# Charging_Indicator_V1_0.net
KiCad netlist of a schematic drawn in EasyEDA
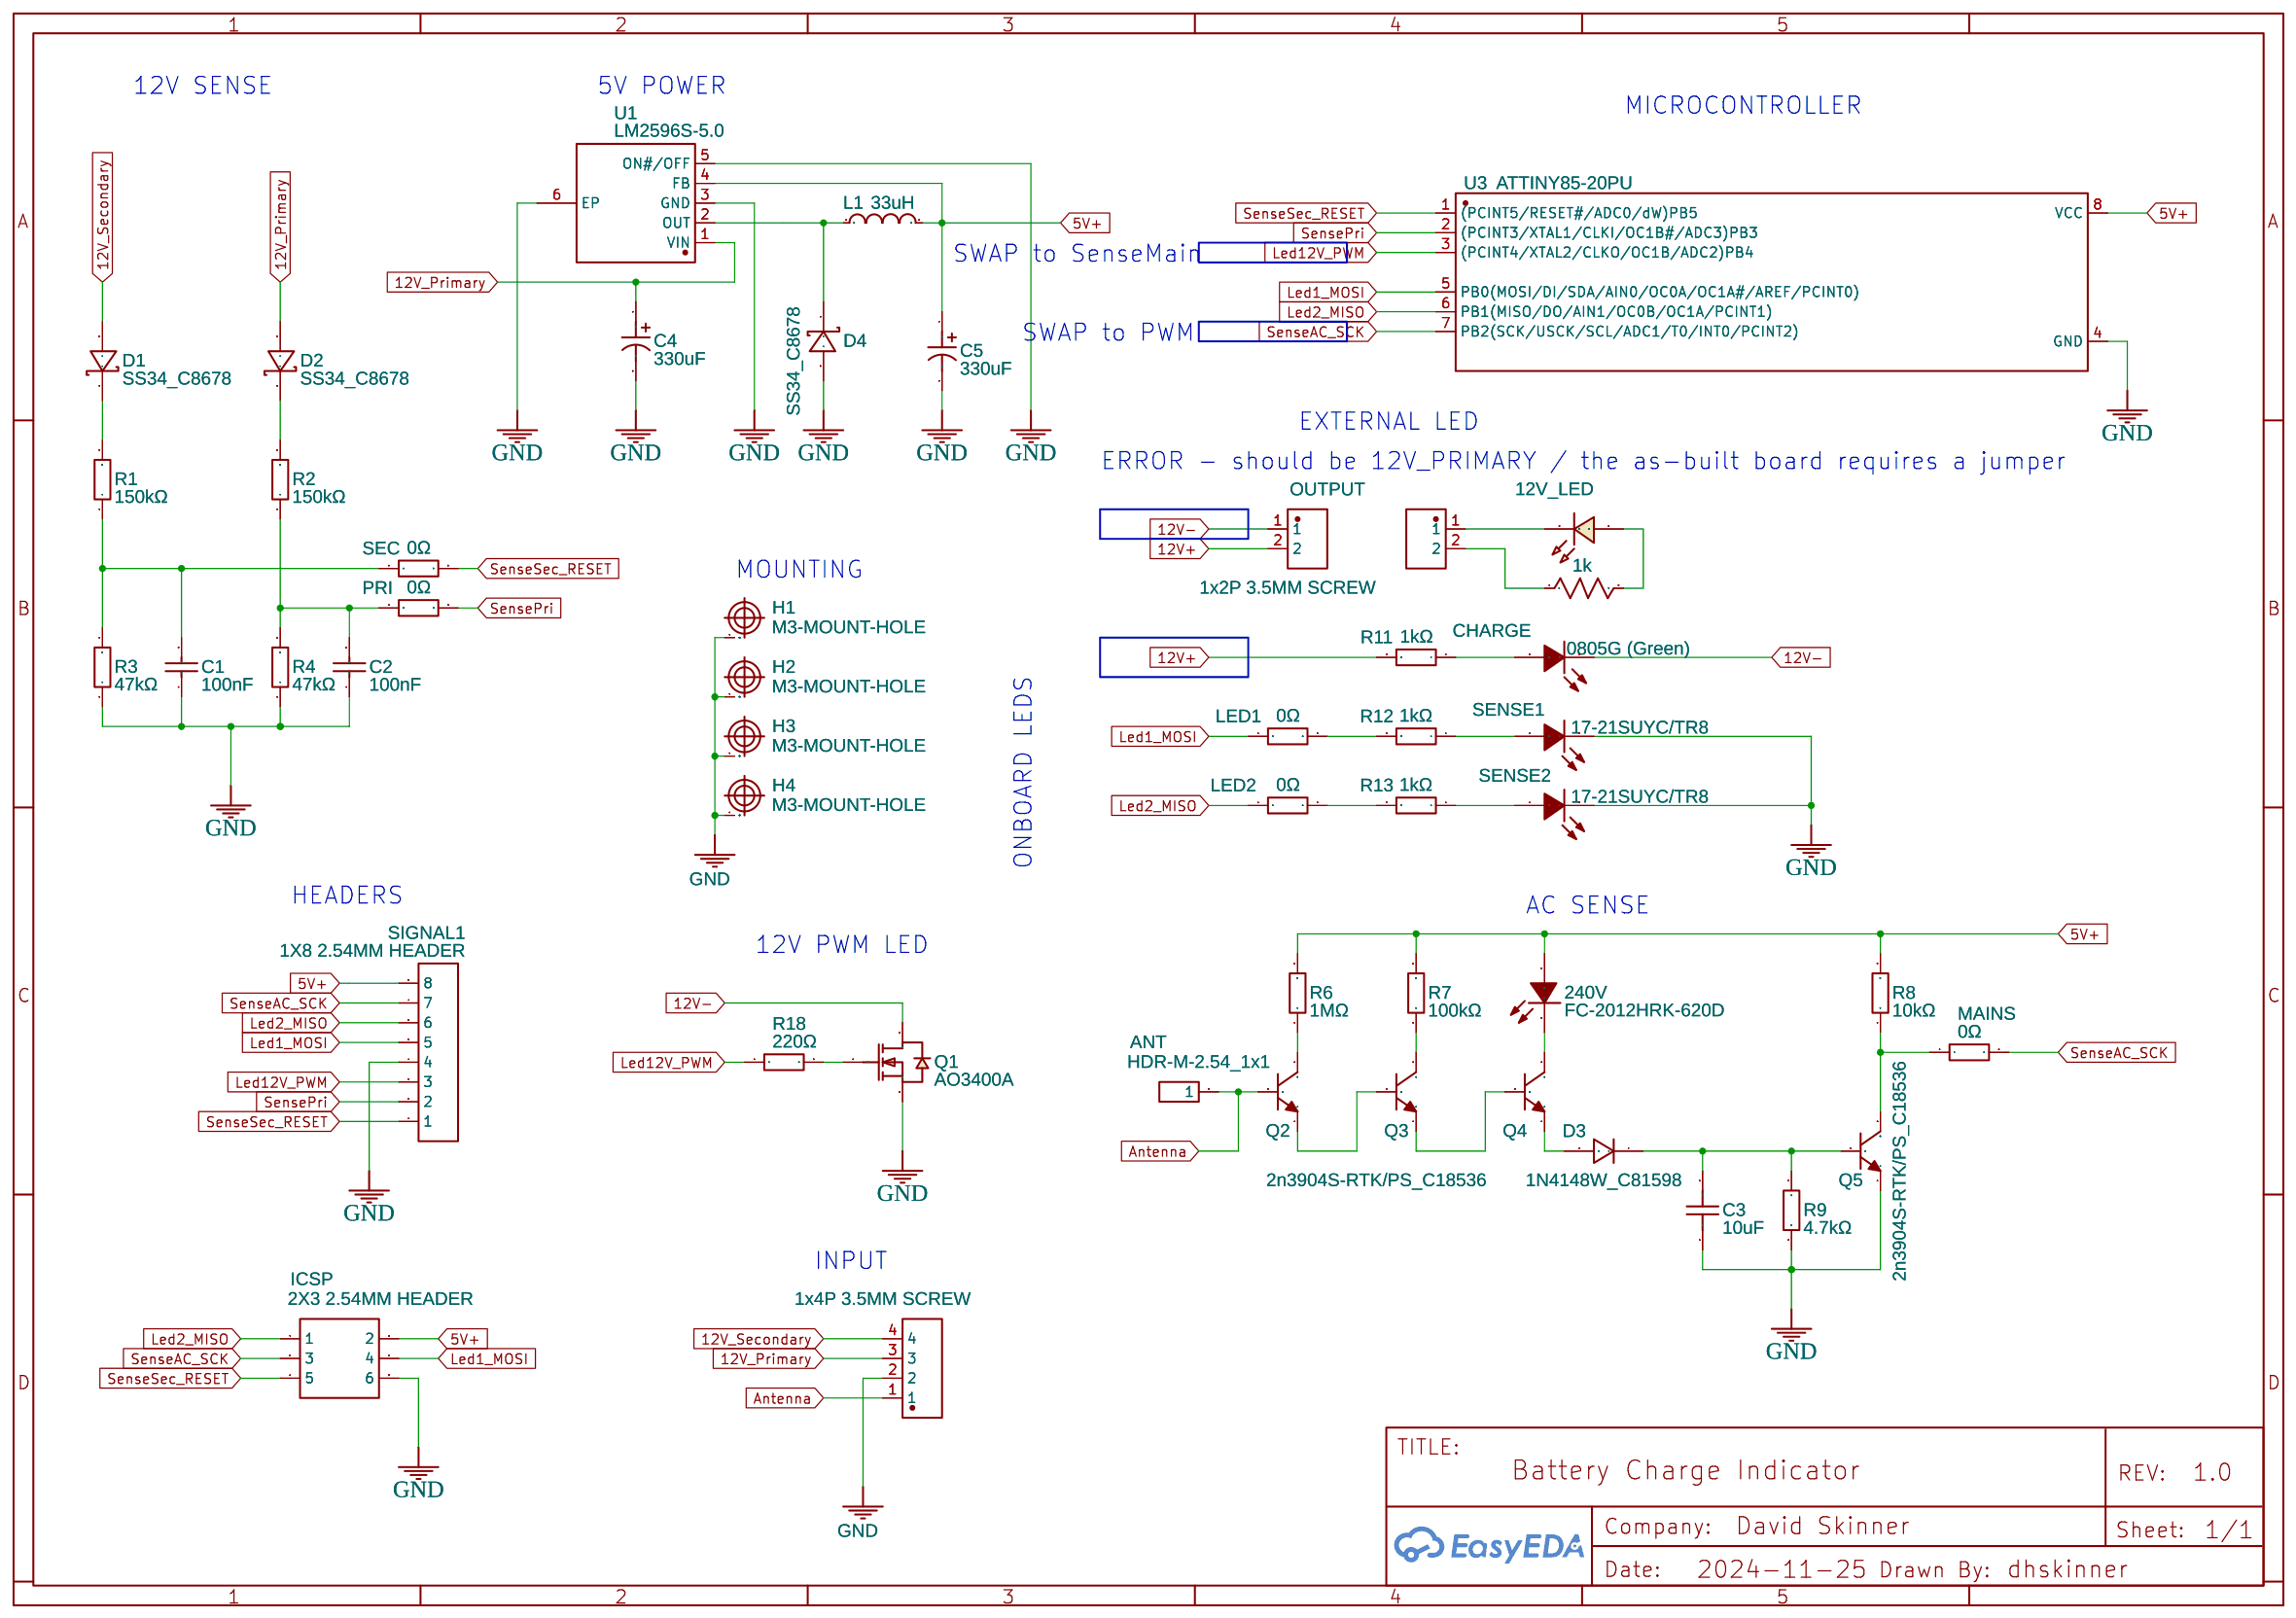
[diagram p0: Sheet_1]
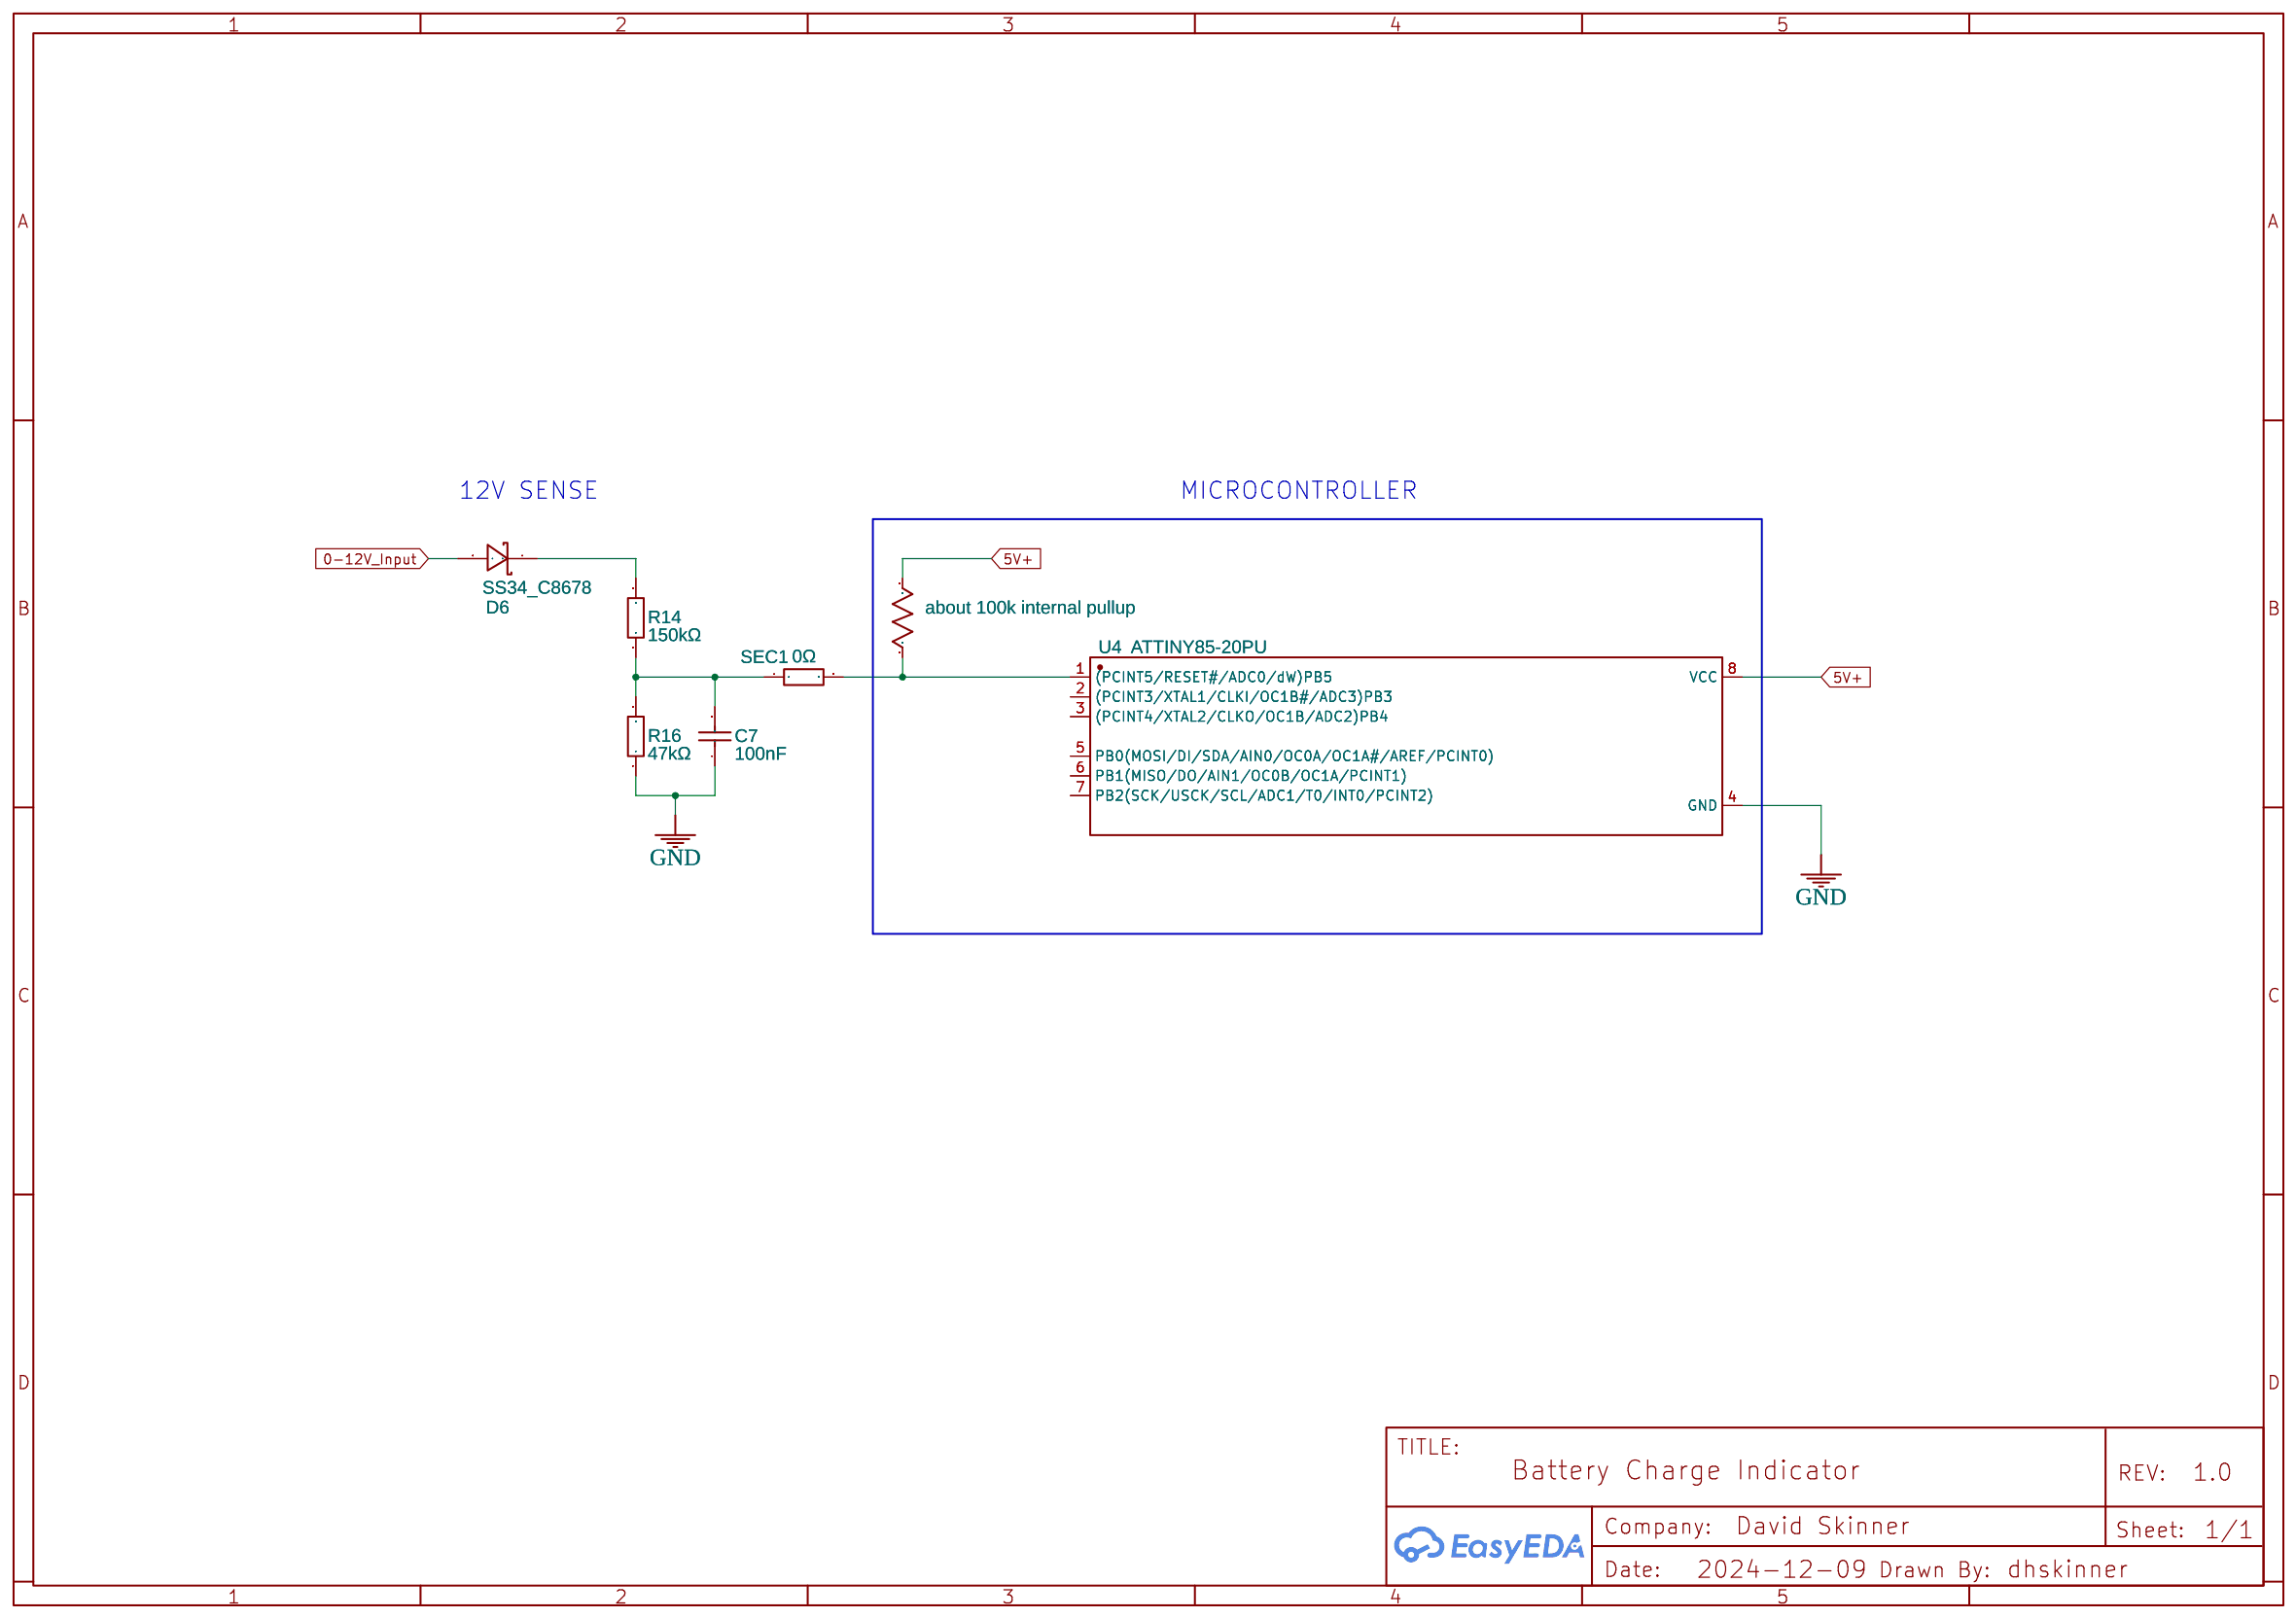
[diagram p1: Sheet_2]
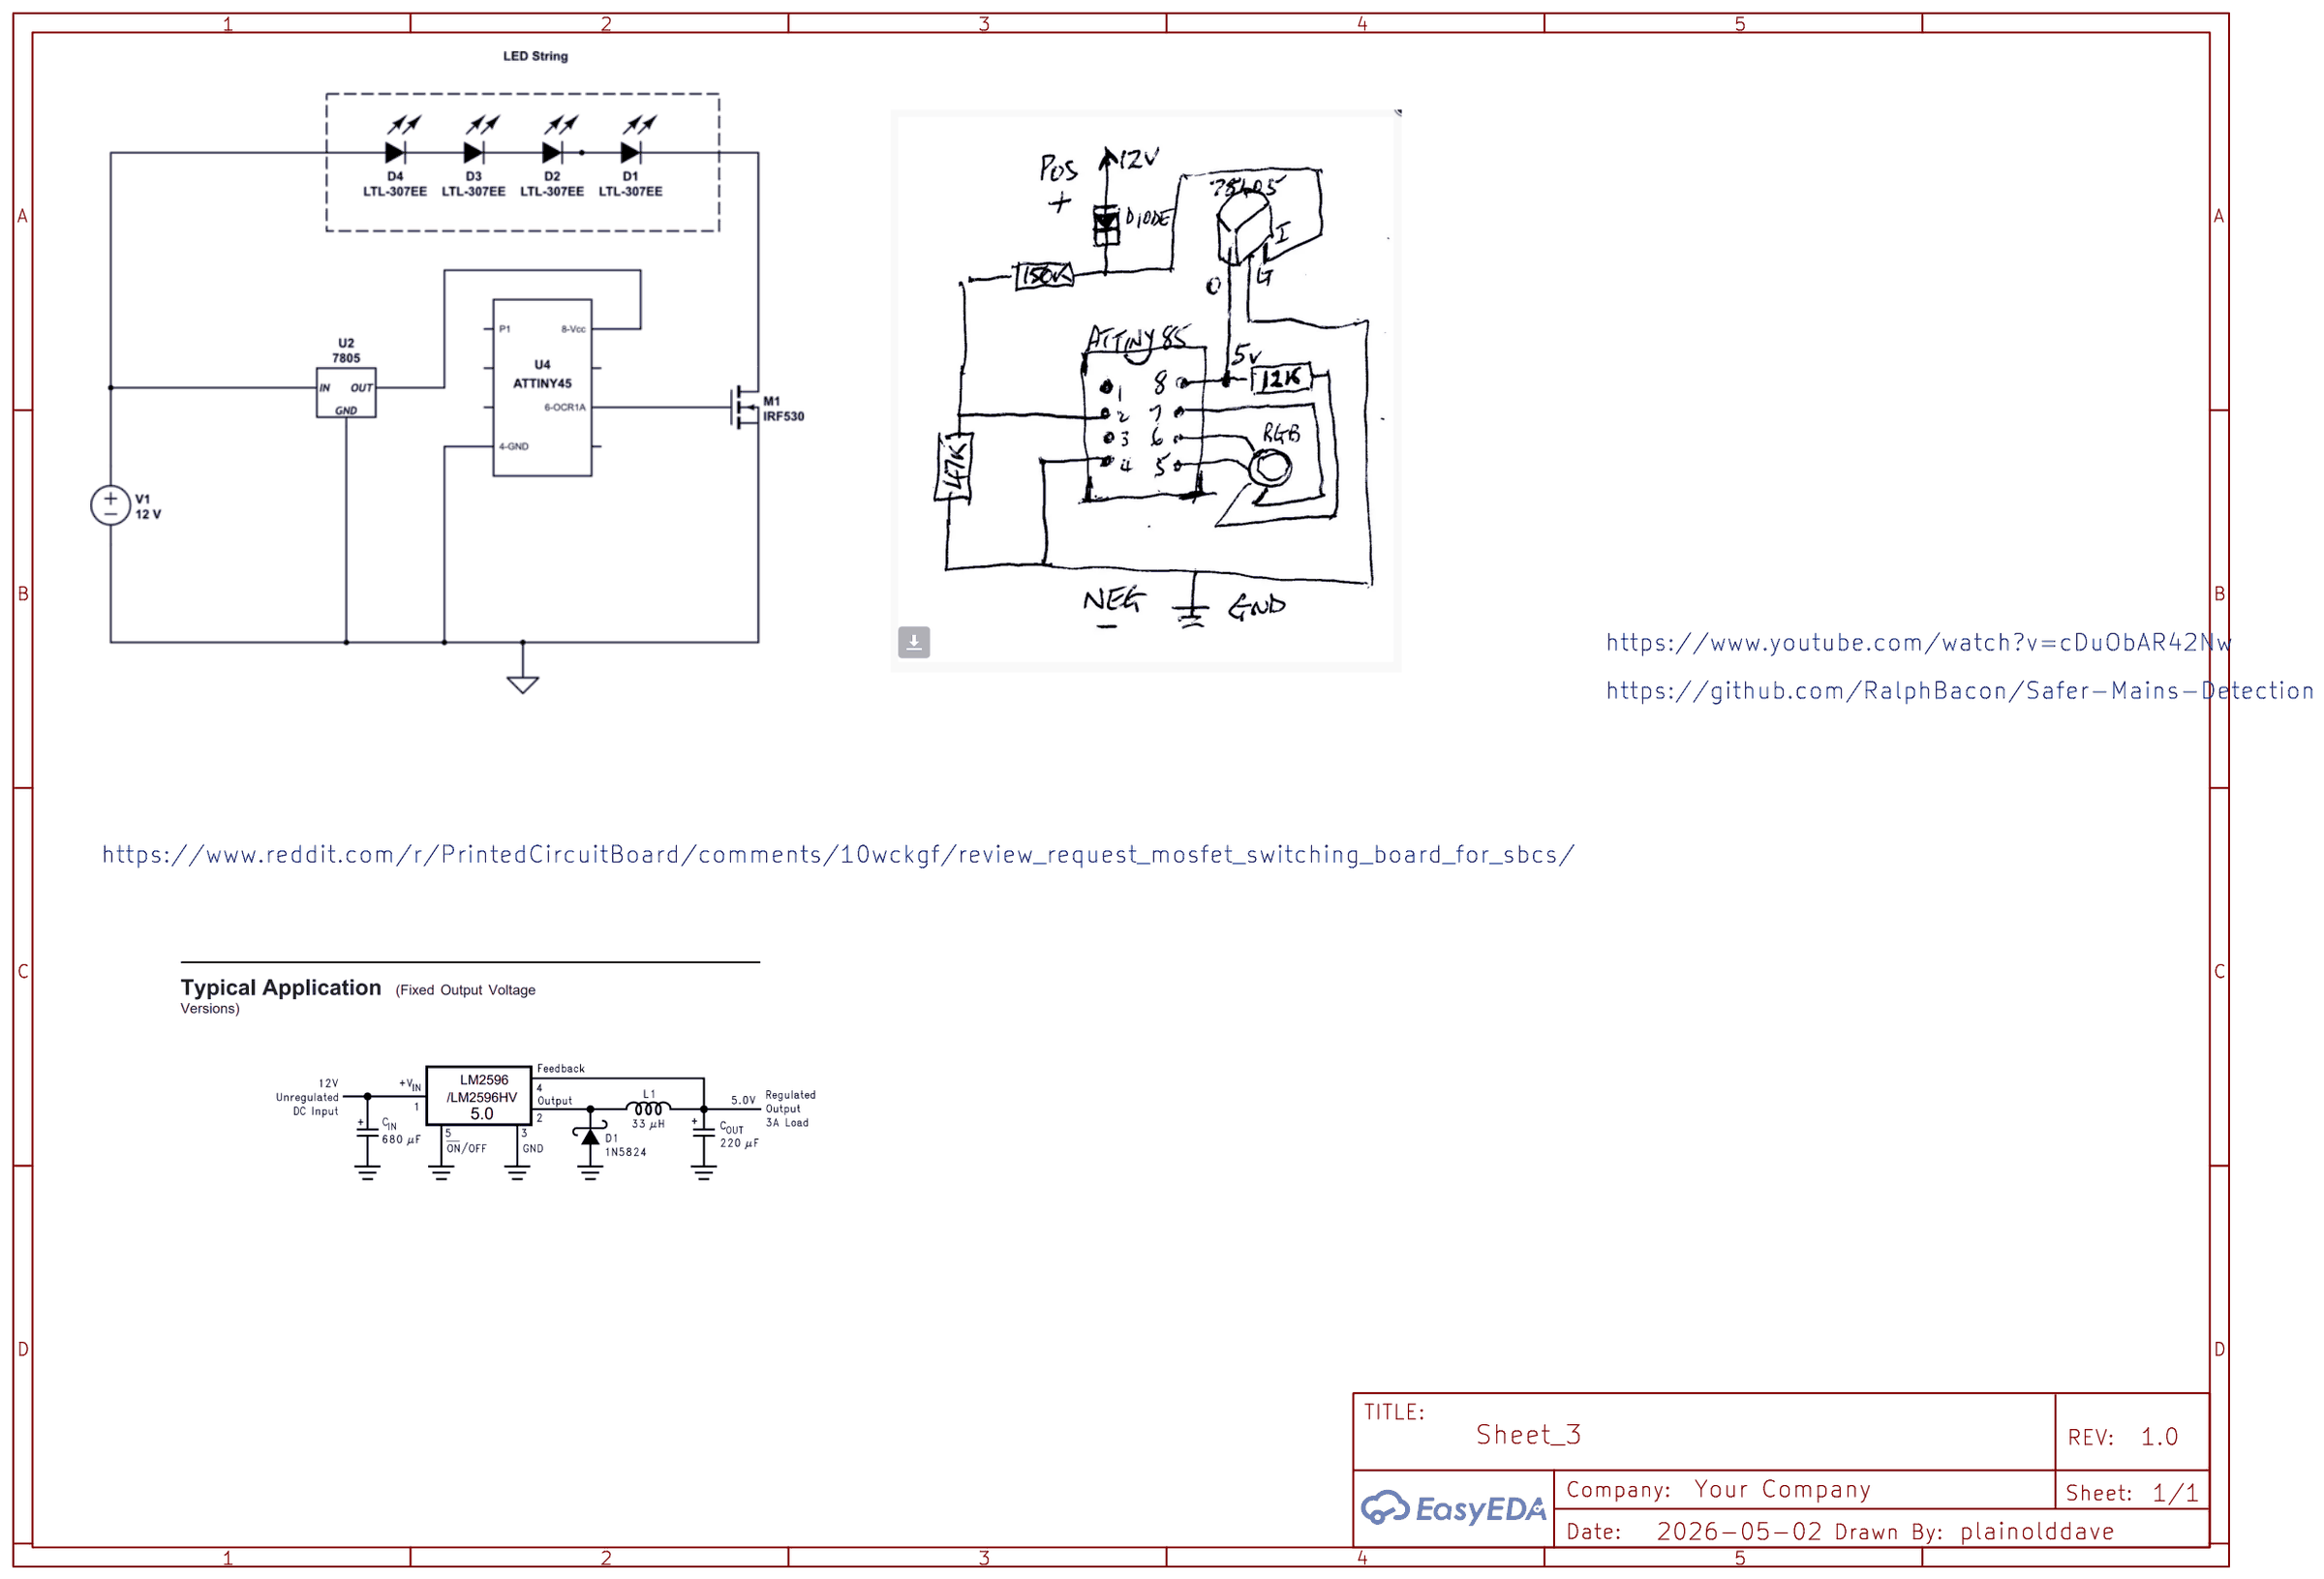
[diagram p2: Notes]

(export (version "E")
  (design (tool "Eeschema 10.0.6"))
  (components
    (comp (ref "12V_LED")
      (value "LED-TH-5mm_G")
      (fields
        (field (name "Manufacturer Part") "333-2SYGD/S530-E2")
        (field (name "Manufacturer") "EVERLIGHT(台湾亿光)")
      )
      (libsource (lib "") (part "LED-TH-5mm_G"))
    )
    (comp (ref "240V")
      (value "FC-2012HRK-620D")
      (fields (field (name "Manufacturer Part") "NCD0805R1") (field (name "Manufacturer") "国星光电"))
      (libsource (lib "") (part "FC-2012HRK-620D"))
    )
    (comp (ref "ANT") (value "HDR-M-2.54_1x1") (libsource (lib "") (part "HDR-M-2.54_1x1")))
    (comp (ref "C1")
      (value "100nF")
      (fields
        (field (name "Manufacturer Part") "CL21B104KCFNNNE")
        (field (name "Manufacturer") "SAMSUNG(三星)")
      )
      (libsource (lib "") (part "CL21B104KCFNNNE"))
    )
    (comp (ref "C2")
      (value "100nF")
      (fields
        (field (name "Manufacturer Part") "CL21B104KCFNNNE")
        (field (name "Manufacturer") "SAMSUNG(三星)")
      )
      (libsource (lib "") (part "CL21B104KCFNNNE"))
    )
    (comp (ref "C3")
      (value "10uF")
      (fields
        (field (name "Manufacturer Part") "CL10A106MA8NRNC")
        (field (name "Manufacturer") "SAMSUNG(三星)")
      )
      (libsource (lib "") (part "CL10A106MA8NRNC"))
    )
    (comp (ref "C4")
      (value "330uF")
      (fields (field (name "Manufacturer Part") "HV0J337M0605PZ") (field (name "Manufacturer") "HONOR(荣誉)"))
      (libsource (lib "") (part "HV0J337M0605PZ"))
    )
    (comp (ref "C5")
      (value "330uF")
      (fields (field (name "Manufacturer Part") "HV0J337M0605PZ") (field (name "Manufacturer") "HONOR(荣誉)"))
      (libsource (lib "") (part "HV0J337M0605PZ"))
    )
    (comp (ref "CHARGE")
      (value "0805G (Green)")
      (fields (field (name "Manufacturer Part") "KT-0805G") (field (name "Manufacturer") "KENTO"))
      (libsource (lib "") (part "0805G (Green)"))
    )
    (comp (ref "D1")
      (value "SS34_C8678")
      (fields (field (name "Manufacturer Part") "SS34") (field (name "Manufacturer") "MDD(辰达半导体)"))
      (libsource (lib "") (part "SS34_C8678_1"))
    )
    (comp (ref "D2")
      (value "SS34_C8678")
      (fields (field (name "Manufacturer Part") "SS34") (field (name "Manufacturer") "MDD(辰达半导体)"))
      (libsource (lib "") (part "SS34_C8678_1"))
    )
    (comp (ref "D3")
      (value "1N4148W_C81598")
      (fields (field (name "Manufacturer Part") "1N4148W") (field (name "Manufacturer") "ST(先科)"))
      (libsource (lib "") (part "1N4148W_C81598"))
    )
    (comp (ref "D4")
      (value "SS34_C8678")
      (fields (field (name "Manufacturer Part") "SS34") (field (name "Manufacturer") "MDD(辰达半导体)"))
      (libsource (lib "") (part "SS34_C8678"))
    )
    (comp (ref "H1") (value "M3-MOUNT-HOLE") (libsource (lib "") (part "M3-MOUNT-HOLE")))
    (comp (ref "H2") (value "M3-MOUNT-HOLE") (libsource (lib "") (part "M3-MOUNT-HOLE")))
    (comp (ref "H3") (value "M3-MOUNT-HOLE") (libsource (lib "") (part "M3-MOUNT-HOLE")))
    (comp (ref "H4") (value "M3-MOUNT-HOLE") (libsource (lib "") (part "M3-MOUNT-HOLE")))
    (comp (ref "ICSP") (value "2X3 2.54MM HEADER") (libsource (lib "") (part "HDR-M-2.54_2x3")))
    (comp (ref "INPUT")
      (value "1x4P 3.5MM SCREW")
      (fields (field (name "Manufacturer Part") "XY350V-3.5-4P") (field (name "Manufacturer") "--"))
      (libsource (lib "") (part "XY350V-3.5-4P"))
    )
    (comp (ref "L1")
      (value "33uH")
      (fields
        (field (name "Manufacturer Part") "SLH1207S330MTT")
        (field (name "Manufacturer") "Sunltech(韩国顺磁)")
      )
      (libsource (lib "") (part "SLH1207S330MTT"))
    )
    (comp (ref "LED1")
      (value "0Ω")
      (fields
        (field (name "Manufacturer Part") "0603WAF0000T5E")
        (field (name "Manufacturer") "UNI-ROYAL(厚声)")
      )
      (libsource (lib "") (part "0603WAF0000T5E_3"))
    )
    (comp (ref "LED2")
      (value "0Ω")
      (fields
        (field (name "Manufacturer Part") "0603WAF0000T5E")
        (field (name "Manufacturer") "UNI-ROYAL(厚声)")
      )
      (libsource (lib "") (part "0603WAF0000T5E_3"))
    )
    (comp (ref "MAINS")
      (value "0Ω")
      (fields
        (field (name "Manufacturer Part") "0603WAF0000T5E")
        (field (name "Manufacturer") "UNI-ROYAL(厚声)")
      )
      (libsource (lib "") (part "0603WAF0000T5E_2"))
    )
    (comp (ref "OUTPUT")
      (value "1x2P 3.5MM SCREW")
      (fields (field (name "Manufacturer Part") "JL124D-35002G01") (field (name "Manufacturer") "JILN(锦凌)"))
      (libsource (lib "") (part "JL124D-35002G01"))
    )
    (comp (ref "PRI")
      (value "0Ω")
      (fields
        (field (name "Manufacturer Part") "0603WAF0000T5E")
        (field (name "Manufacturer") "UNI-ROYAL(厚声)")
      )
      (libsource (lib "") (part "0603WAF0000T5E_1"))
    )
    (comp (ref "Q1")
      (value "AO3400A")
      (fields (field (name "Manufacturer") "AOS"))
      (libsource (lib "") (part "AO3400A"))
    )
    (comp (ref "Q2")
      (value "2n3904S-RTK/PS_C18536")
      (fields (field (name "Manufacturer Part") "2N3904S-RTK/PS") (field (name "Manufacturer") "KEC"))
      (libsource (lib "") (part "2n3904S-RTK/PS_C18536"))
    )
    (comp (ref "Q3")
      (value "2n3904S-RTK/PS_C18536")
      (fields (field (name "Manufacturer Part") "2N3904S-RTK/PS") (field (name "Manufacturer") "KEC"))
      (libsource (lib "") (part "2n3904S-RTK/PS_C18536"))
    )
    (comp (ref "Q4")
      (value "2n3904S-RTK/PS_C18536")
      (fields (field (name "Manufacturer Part") "2N3904S-RTK/PS") (field (name "Manufacturer") "KEC"))
      (libsource (lib "") (part "2n3904S-RTK/PS_C18536"))
    )
    (comp (ref "Q5")
      (value "2n3904S-RTK/PS_C18536")
      (fields (field (name "Manufacturer Part") "2N3904S-RTK/PS") (field (name "Manufacturer") "KEC"))
      (libsource (lib "") (part "2n3904S-RTK/PS_C18536"))
    )
    (comp (ref "R1")
      (value "150kΩ")
      (fields
        (field (name "Manufacturer Part") "0805W8F1503T5E")
        (field (name "Manufacturer") "UNI-ROYAL(厚声)")
      )
      (libsource (lib "") (part "0805W8F1503T5E"))
    )
    (comp (ref "R2")
      (value "150kΩ")
      (fields
        (field (name "Manufacturer Part") "0805W8F1503T5E")
        (field (name "Manufacturer") "UNI-ROYAL(厚声)")
      )
      (libsource (lib "") (part "0805W8F1503T5E"))
    )
    (comp (ref "R3")
      (value "47kΩ")
      (fields
        (field (name "Manufacturer Part") "0805W8F4702T5E")
        (field (name "Manufacturer") "UNI-ROYAL(厚声)")
      )
      (libsource (lib "") (part "0805W8F4702T5E"))
    )
    (comp (ref "R4")
      (value "47kΩ")
      (fields
        (field (name "Manufacturer Part") "0805W8F4702T5E")
        (field (name "Manufacturer") "UNI-ROYAL(厚声)")
      )
      (libsource (lib "") (part "0805W8F4702T5E"))
    )
    (comp (ref "R5") (value "1k") (libsource (lib "") (part "R_AXIAL-0.4_US")))
    (comp (ref "R6")
      (value "1MΩ")
      (fields
        (field (name "Manufacturer Part") "0603WAF1004T5E")
        (field (name "Manufacturer") "UNI-ROYAL(厚声)")
      )
      (libsource (lib "") (part "0603WAF1004T5E"))
    )
    (comp (ref "R7")
      (value "100kΩ")
      (fields
        (field (name "Manufacturer Part") "1206W4F1003T5E")
        (field (name "Manufacturer") "UNI-ROYAL(厚声)")
      )
      (libsource (lib "") (part "1206W4F1003T5E"))
    )
    (comp (ref "R8")
      (value "10kΩ")
      (fields
        (field (name "Manufacturer Part") "0603WAF1002T5E")
        (field (name "Manufacturer") "UNI-ROYAL(厚声)")
      )
      (libsource (lib "") (part "0603WAF1002T5E"))
    )
    (comp (ref "R9")
      (value "4.7kΩ")
      (fields
        (field (name "Manufacturer Part") "1206W4F4701T5E")
        (field (name "Manufacturer") "UNI-ROYAL(厚声)")
      )
      (libsource (lib "") (part "1206W4F4701T5E"))
    )
    (comp (ref "R11")
      (value "1kΩ")
      (fields
        (field (name "Manufacturer Part") "0805W8F1001T5E")
        (field (name "Manufacturer") "UNI-ROYAL(厚声)")
      )
      (libsource (lib "") (part "0805W8F1001T5E"))
    )
    (comp (ref "R12")
      (value "1kΩ")
      (fields
        (field (name "Manufacturer Part") "0805W8F1001T5E")
        (field (name "Manufacturer") "UNI-ROYAL(厚声)")
      )
      (libsource (lib "") (part "0805W8F1001T5E"))
    )
    (comp (ref "R13")
      (value "1kΩ")
      (fields
        (field (name "Manufacturer Part") "0805W8F1001T5E")
        (field (name "Manufacturer") "UNI-ROYAL(厚声)")
      )
      (libsource (lib "") (part "0805W8F1001T5E"))
    )
    (comp (ref "R18")
      (value "220Ω")
      (fields
        (field (name "Manufacturer Part") "0603WAF2200T5E")
        (field (name "Manufacturer") "UNI-ROYAL(厚声)")
      )
      (libsource (lib "") (part "0603WAF2200T5E"))
    )
    (comp (ref "SEC")
      (value "0Ω")
      (fields
        (field (name "Manufacturer Part") "0603WAF0000T5E")
        (field (name "Manufacturer") "UNI-ROYAL(厚声)")
      )
      (libsource (lib "") (part "0603WAF0000T5E"))
    )
    (comp (ref "SENSE1")
      (value "17-21SUYC/TR8")
      (fields (field (name "Manufacturer Part") "KT-0805黄灯") (field (name "Manufacturer") "KENTO"))
      (libsource (lib "") (part "17-21SUYC/TR8"))
    )
    (comp (ref "SENSE2")
      (value "17-21SUYC/TR8")
      (fields (field (name "Manufacturer Part") "KT-0805黄灯") (field (name "Manufacturer") "KENTO"))
      (libsource (lib "") (part "17-21SUYC/TR8"))
    )
    (comp (ref "SIGNAL1") (value "1X8 2.54MM HEADER") (libsource (lib "") (part "HDR-M-2.54_1x8")))
    (comp (ref "U1")
      (value "LM2596S-5.0")
      (fields (field (name "Manufacturer") "UMW(友台半导体)"))
      (libsource (lib "") (part "LM2596S-5.0"))
    )
    (comp (ref "U2")
      (value "JL124D-35002G01")
      (fields (field (name "Manufacturer") "JILN(锦凌)"))
      (libsource (lib "") (part "JL124D-35002G01_1"))
    )
    (comp (ref "U3")
      (value "ATTINY85-20PU")
      (fields (field (name "Manufacturer") "MICROCHIP(美国微芯)"))
      (libsource (lib "") (part "ATTINY85-20PU"))
    )
    (comp (ref "C7")
      (value "100nF")
      (fields
        (field (name "Manufacturer Part") "CL21B104KCFNNNE")
        (field (name "Manufacturer") "SAMSUNG(三星)")
      )
      (libsource (lib "") (part "CL21B104KCFNNNE"))
    )
    (comp (ref "D6")
      (value "SS34_C8678")
      (fields (field (name "Manufacturer Part") "SS34") (field (name "Manufacturer") "MDD(辰达半导体)"))
      (libsource (lib "") (part "SS34_C8678"))
    )
    (comp (ref "R10") (value "about 100k internal pullup") (libsource (lib "") (part "R_0603_US")))
    (comp (ref "R14")
      (value "150kΩ")
      (fields
        (field (name "Manufacturer Part") "0805W8F1503T5E")
        (field (name "Manufacturer") "UNI-ROYAL(厚声)")
      )
      (libsource (lib "") (part "0805W8F1503T5E"))
    )
    (comp (ref "R16")
      (value "47kΩ")
      (fields
        (field (name "Manufacturer Part") "0805W8F4702T5E")
        (field (name "Manufacturer") "UNI-ROYAL(厚声)")
      )
      (libsource (lib "") (part "0805W8F4702T5E"))
    )
    (comp (ref "SEC1")
      (value "0Ω")
      (fields
        (field (name "Manufacturer Part") "0603WAF0000T5E")
        (field (name "Manufacturer") "UNI-ROYAL(厚声)")
      )
      (libsource (lib "") (part "0603WAF0000T5E"))
    )
    (comp (ref "U4")
      (value "ATTINY85-20PU")
      (fields (field (name "Manufacturer") "MICROCHIP(美国微芯)"))
      (libsource (lib "") (part "ATTINY85-20PU"))
    )
  )
  (nets
    (net (code "1") (name "0-12V_Input") (class "Default")
      (node (ref "D6") (pin "2") (pinfunction "A_2") (pintype "unspecified"))
    )
    (net (code "2") (name "5V+") (class "Default")
      (node (ref "240V") (pin "1") (pinfunction "+_1") (pintype "unspecified"))
      (node (ref "C5") (pin "1") (pinfunction "1_1") (pintype "input"))
      (node (ref "ICSP") (pin "2") (pinfunction "2_2") (pintype "input"))
      (node (ref "L1") (pin "2") (pinfunction "2_2") (pintype "unspecified"))
      (node (ref "R10") (pin "2") (pinfunction "2_2") (pintype "unspecified"))
      (node (ref "R6") (pin "2") (pinfunction "2_2") (pintype "input"))
      (node (ref "R7") (pin "2") (pinfunction "2_2") (pintype "input"))
      (node (ref "R8") (pin "2") (pinfunction "2_2") (pintype "input"))
      (node (ref "SIGNAL1") (pin "8") (pinfunction "8_8") (pintype "unspecified"))
      (node (ref "U1") (pin "4") (pinfunction "FB_4") (pintype "unspecified"))
      (node (ref "U3") (pin "8") (pinfunction "VCC_8") (pintype "unspecified"))
      (node (ref "U4") (pin "8") (pinfunction "VCC_8") (pintype "unspecified"))
    )
    (net (code "3") (name "12V+") (class "Default")
      (node (ref "OUTPUT") (pin "2") (pinfunction "2_2") (pintype "unspecified"))
      (node (ref "R11") (pin "2") (pinfunction "2_2") (pintype "input"))
    )
    (net (code "4") (name "12V-") (class "Default")
      (node (ref "CHARGE") (pin "2") (pinfunction "K_2") (pintype "unspecified"))
      (node (ref "OUTPUT") (pin "1") (pinfunction "1_1") (pintype "unspecified"))
      (node (ref "Q1") (pin "3") (pinfunction "D_3") (pintype "unspecified"))
    )
    (net (code "5") (name "12V_Primary") (class "Default")
      (node (ref "C4") (pin "1") (pinfunction "1_1") (pintype "input"))
      (node (ref "D2") (pin "2") (pinfunction "A_2") (pintype "unspecified"))
      (node (ref "INPUT") (pin "3") (pinfunction "3_3") (pintype "unspecified"))
      (node (ref "U1") (pin "1") (pinfunction "VIN_1") (pintype "unspecified"))
    )
    (net (code "6") (name "12V_Secondary") (class "Default")
      (node (ref "D1") (pin "2") (pinfunction "A_2") (pintype "unspecified"))
      (node (ref "INPUT") (pin "4") (pinfunction "4_4") (pintype "unspecified"))
    )
    (net (code "7") (name "Antenna") (class "Default")
      (node (ref "ANT") (pin "1") (pinfunction "1_1") (pintype "input"))
      (node (ref "INPUT") (pin "1") (pinfunction "1_1") (pintype "unspecified"))
      (node (ref "Q2") (pin "2") (pinfunction "B_2") (pintype "input"))
    )
    (net (code "8") (name "GND") (class "Default")
      (node (ref "C1") (pin "1") (pinfunction "1_1") (pintype "input"))
      (node (ref "C2") (pin "1") (pinfunction "1_1") (pintype "input"))
      (node (ref "C3") (pin "1") (pinfunction "1_1") (pintype "unspecified"))
      (node (ref "C4") (pin "2") (pinfunction "2_2") (pintype "input"))
      (node (ref "C5") (pin "2") (pinfunction "2_2") (pintype "input"))
      (node (ref "C7") (pin "1") (pinfunction "1_1") (pintype "input"))
      (node (ref "D4") (pin "2") (pinfunction "A_2") (pintype "unspecified"))
      (node (ref "H1") (pin "1") (pinfunction "GND_1") (pintype "passive"))
      (node (ref "H2") (pin "1") (pinfunction "GND_1") (pintype "passive"))
      (node (ref "H3") (pin "1") (pinfunction "GND_1") (pintype "passive"))
      (node (ref "H4") (pin "1") (pinfunction "GND_1") (pintype "passive"))
      (node (ref "ICSP") (pin "6") (pinfunction "6_6") (pintype "input"))
      (node (ref "INPUT") (pin "2") (pinfunction "2_2") (pintype "unspecified"))
      (node (ref "Q1") (pin "2") (pinfunction "S_2") (pintype "unspecified"))
      (node (ref "Q5") (pin "1") (pinfunction "E_1") (pintype "input"))
      (node (ref "R16") (pin "1") (pinfunction "1_1") (pintype "input"))
      (node (ref "R3") (pin "1") (pinfunction "1_1") (pintype "input"))
      (node (ref "R4") (pin "1") (pinfunction "1_1") (pintype "input"))
      (node (ref "R9") (pin "1") (pinfunction "1_1") (pintype "input"))
      (node (ref "SENSE1") (pin "2") (pinfunction "-_2") (pintype "unspecified"))
      (node (ref "SENSE2") (pin "2") (pinfunction "-_2") (pintype "unspecified"))
      (node (ref "SIGNAL1") (pin "4") (pinfunction "4_4") (pintype "unspecified"))
      (node (ref "U1") (pin "3") (pinfunction "GND_3") (pintype "unspecified"))
      (node (ref "U1") (pin "5") (pinfunction "ON#/OFF_5") (pintype "unspecified"))
      (node (ref "U1") (pin "6") (pinfunction "EP_6") (pintype "unspecified"))
      (node (ref "U3") (pin "4") (pinfunction "GND_4") (pintype "unspecified"))
      (node (ref "U4") (pin "4") (pinfunction "GND_4") (pintype "unspecified"))
    )
    (net (code "9") (name "Led1_MOSI") (class "Default")
      (node (ref "ICSP") (pin "4") (pinfunction "4_4") (pintype "input"))
      (node (ref "LED1") (pin "1") (pinfunction "1_1") (pintype "input"))
      (node (ref "SIGNAL1") (pin "5") (pinfunction "5_5") (pintype "unspecified"))
      (node (ref "U3") (pin "5") (pinfunction "PB0(MOSI/DI/SDA/AIN0/OC0A/OC1A#/AREF/PCINT0)_5") (pintype "unspecified"))
    )
    (net (code "10") (name "Led2_MISO") (class "Default")
      (node (ref "ICSP") (pin "1") (pinfunction "1_1") (pintype "input"))
      (node (ref "LED2") (pin "1") (pinfunction "1_1") (pintype "input"))
      (node (ref "SIGNAL1") (pin "6") (pinfunction "6_6") (pintype "unspecified"))
      (node (ref "U3") (pin "6") (pinfunction "PB1(MISO/DO/AIN1/OC0B/OC1A/PCINT1)_6") (pintype "unspecified"))
    )
    (net (code "11") (name "Led12V_PWM") (class "Default")
      (node (ref "R18") (pin "1") (pinfunction "1_1") (pintype "input"))
      (node (ref "SIGNAL1") (pin "3") (pinfunction "3_3") (pintype "unspecified"))
      (node (ref "U3") (pin "3") (pinfunction "(PCINT4/XTAL2/CLKO/OC1B/ADC2)PB4_3") (pintype "unspecified"))
    )
    (net (code "12") (name "Net-(12V_LED-Pad1)") (class "Default")
      (node (ref "12V_LED") (pin "1") (pinfunction "1_1") (pintype "unspecified"))
      (node (ref "R5") (pin "2") (pinfunction "2_2") (pintype "unspecified"))
    )
    (net (code "13") (name "Net-(12V_LED-Pad2)") (class "Default")
      (node (ref "12V_LED") (pin "2") (pinfunction "2_2") (pintype "unspecified"))
      (node (ref "U2") (pin "1") (pinfunction "1_1") (pintype "unspecified"))
    )
    (net (code "14") (name "Net-(240V--)") (class "Default")
      (node (ref "240V") (pin "2") (pinfunction "-_2") (pintype "unspecified"))
      (node (ref "Q4") (pin "3") (pinfunction "C_3") (pintype "input"))
    )
    (net (code "15") (name "Net-(C1-Pad2)") (class "Default")
      (node (ref "C1") (pin "2") (pinfunction "2_2") (pintype "input"))
      (node (ref "R1") (pin "1") (pinfunction "1_1") (pintype "input"))
      (node (ref "R3") (pin "2") (pinfunction "2_2") (pintype "input"))
      (node (ref "SEC") (pin "1") (pinfunction "1_1") (pintype "input"))
    )
    (net (code "16") (name "Net-(C2-Pad2)") (class "Default")
      (node (ref "C2") (pin "2") (pinfunction "2_2") (pintype "input"))
      (node (ref "PRI") (pin "1") (pinfunction "1_1") (pintype "input"))
      (node (ref "R2") (pin "1") (pinfunction "1_1") (pintype "input"))
      (node (ref "R4") (pin "2") (pinfunction "2_2") (pintype "input"))
    )
    (net (code "17") (name "Net-(C7-Pad2)") (class "Default")
      (node (ref "C7") (pin "2") (pinfunction "2_2") (pintype "input"))
      (node (ref "R14") (pin "1") (pinfunction "1_1") (pintype "input"))
      (node (ref "R16") (pin "2") (pinfunction "2_2") (pintype "input"))
      (node (ref "SEC1") (pin "1") (pinfunction "1_1") (pintype "input"))
    )
    (net (code "18") (name "Net-(CHARGE-A)") (class "Default")
      (node (ref "CHARGE") (pin "1") (pinfunction "A_1") (pintype "unspecified"))
      (node (ref "R11") (pin "1") (pinfunction "1_1") (pintype "input"))
    )
    (net (code "19") (name "Net-(D1-K)") (class "Default")
      (node (ref "D1") (pin "1") (pinfunction "K_1") (pintype "unspecified"))
      (node (ref "R1") (pin "2") (pinfunction "2_2") (pintype "input"))
    )
    (net (code "20") (name "Net-(D2-K)") (class "Default")
      (node (ref "D2") (pin "1") (pinfunction "K_1") (pintype "unspecified"))
      (node (ref "R2") (pin "2") (pinfunction "2_2") (pintype "input"))
    )
    (net (code "21") (name "Net-(D3-A)") (class "Default")
      (node (ref "D3") (pin "2") (pinfunction "A_2") (pintype "unspecified"))
      (node (ref "Q4") (pin "1") (pinfunction "E_1") (pintype "input"))
    )
    (net (code "22") (name "Net-(D3-K)") (class "Default")
      (node (ref "C3") (pin "2") (pinfunction "2_2") (pintype "unspecified"))
      (node (ref "D3") (pin "1") (pinfunction "K_1") (pintype "unspecified"))
      (node (ref "Q5") (pin "2") (pinfunction "B_2") (pintype "input"))
      (node (ref "R9") (pin "2") (pinfunction "2_2") (pintype "input"))
    )
    (net (code "23") (name "Net-(D4-K)") (class "Default")
      (node (ref "D4") (pin "1") (pinfunction "K_1") (pintype "unspecified"))
      (node (ref "L1") (pin "1") (pinfunction "1_1") (pintype "unspecified"))
      (node (ref "U1") (pin "2") (pinfunction "OUT_2") (pintype "unspecified"))
    )
    (net (code "24") (name "Net-(D6-K)") (class "Default")
      (node (ref "D6") (pin "1") (pinfunction "K_1") (pintype "unspecified"))
      (node (ref "R14") (pin "2") (pinfunction "2_2") (pintype "input"))
    )
    (net (code "25") (name "Net-(LED1-Pad2)") (class "Default")
      (node (ref "LED1") (pin "2") (pinfunction "2_2") (pintype "input"))
      (node (ref "R12") (pin "2") (pinfunction "2_2") (pintype "input"))
    )
    (net (code "26") (name "Net-(LED2-Pad2)") (class "Default")
      (node (ref "LED2") (pin "2") (pinfunction "2_2") (pintype "input"))
      (node (ref "R13") (pin "2") (pinfunction "2_2") (pintype "input"))
    )
    (net (code "27") (name "Net-(Q1-G)") (class "Default")
      (node (ref "Q1") (pin "1") (pinfunction "G_1") (pintype "unspecified"))
      (node (ref "R18") (pin "2") (pinfunction "2_2") (pintype "input"))
    )
    (net (code "28") (name "Net-(Q2-C)") (class "Default")
      (node (ref "Q2") (pin "3") (pinfunction "C_3") (pintype "input"))
      (node (ref "R6") (pin "1") (pinfunction "1_1") (pintype "input"))
    )
    (net (code "29") (name "Net-(Q2-E)") (class "Default")
      (node (ref "Q2") (pin "1") (pinfunction "E_1") (pintype "input"))
      (node (ref "Q3") (pin "2") (pinfunction "B_2") (pintype "input"))
    )
    (net (code "30") (name "Net-(Q3-C)") (class "Default")
      (node (ref "Q3") (pin "3") (pinfunction "C_3") (pintype "input"))
      (node (ref "R7") (pin "1") (pinfunction "1_1") (pintype "input"))
    )
    (net (code "31") (name "Net-(Q3-E)") (class "Default")
      (node (ref "Q3") (pin "1") (pinfunction "E_1") (pintype "input"))
      (node (ref "Q4") (pin "2") (pinfunction "B_2") (pintype "input"))
    )
    (net (code "32") (name "Net-(Q5-C)") (class "Default")
      (node (ref "MAINS") (pin "1") (pinfunction "1_1") (pintype "input"))
      (node (ref "Q5") (pin "3") (pinfunction "C_3") (pintype "input"))
      (node (ref "R8") (pin "1") (pinfunction "1_1") (pintype "input"))
    )
    (net (code "33") (name "Net-(R5-Pad1)") (class "Default")
      (node (ref "R5") (pin "1") (pinfunction "1_1") (pintype "unspecified"))
      (node (ref "U2") (pin "2") (pinfunction "2_2") (pintype "unspecified"))
    )
    (net (code "34") (name "Net-(SENSE1-+)") (class "Default")
      (node (ref "R12") (pin "1") (pinfunction "1_1") (pintype "input"))
      (node (ref "SENSE1") (pin "1") (pinfunction "+_1") (pintype "unspecified"))
    )
    (net (code "35") (name "Net-(SENSE2-+)") (class "Default")
      (node (ref "R13") (pin "1") (pinfunction "1_1") (pintype "input"))
      (node (ref "SENSE2") (pin "1") (pinfunction "+_1") (pintype "unspecified"))
    )
    (net (code "36") (name "Net-(U4-(PCINT5{slash}RESET#{slash}ADC0{slash}dW)PB5)") (class "Default")
      (node (ref "R10") (pin "1") (pinfunction "1_1") (pintype "unspecified"))
      (node (ref "SEC1") (pin "2") (pinfunction "2_2") (pintype "input"))
      (node (ref "U4") (pin "1") (pinfunction "(PCINT5/RESET#/ADC0/dW)PB5_1") (pintype "unspecified"))
    )
    (net (code "37") (name "SenseAC_SCK") (class "Default")
      (node (ref "ICSP") (pin "3") (pinfunction "3_3") (pintype "input"))
      (node (ref "MAINS") (pin "2") (pinfunction "2_2") (pintype "input"))
      (node (ref "SIGNAL1") (pin "7") (pinfunction "7_7") (pintype "unspecified"))
      (node (ref "U3") (pin "7") (pinfunction "PB2(SCK/USCK/SCL/ADC1/T0/INT0/PCINT2)_7") (pintype "unspecified"))
    )
    (net (code "38") (name "SensePri") (class "Default")
      (node (ref "PRI") (pin "2") (pinfunction "2_2") (pintype "input"))
      (node (ref "SIGNAL1") (pin "2") (pinfunction "2_2") (pintype "unspecified"))
      (node (ref "U3") (pin "2") (pinfunction "(PCINT3/XTAL1/CLKI/OC1B#/ADC3)PB3_2") (pintype "unspecified"))
    )
    (net (code "39") (name "SenseSec_RESET") (class "Default")
      (node (ref "ICSP") (pin "5") (pinfunction "5_5") (pintype "input"))
      (node (ref "SEC") (pin "2") (pinfunction "2_2") (pintype "input"))
      (node (ref "SIGNAL1") (pin "1") (pinfunction "1_1") (pintype "unspecified"))
      (node (ref "U3") (pin "1") (pinfunction "(PCINT5/RESET#/ADC0/dW)PB5_1") (pintype "unspecified"))
    )
    (net (code "40") (name "unconnected-(U4-(PCINT3{slash}XTAL1{slash}CLKI{slash}OC1B#{slash}ADC3)PB3-Pad2)") (class "Default")
      (node (ref "U4") (pin "2") (pinfunction "(PCINT3/XTAL1/CLKI/OC1B#/ADC3)PB3_2") (pintype "unspecified"))
    )
    (net (code "41") (name "unconnected-(U4-(PCINT4{slash}XTAL2{slash}CLKO{slash}OC1B{slash}ADC2)PB4-Pad3)") (class "Default")
      (node (ref "U4") (pin "3") (pinfunction "(PCINT4/XTAL2/CLKO/OC1B/ADC2)PB4_3") (pintype "unspecified"))
    )
    (net (code "42") (name "unconnected-(U4-PB0(MOSI{slash}DI{slash}SDA{slash}AIN0{slash}OC0A{slash}OC1A#{slash}AREF{slash}PCINT0)-Pad5)") (class "Default")
      (node (ref "U4") (pin "5") (pinfunction "PB0(MOSI/DI/SDA/AIN0/OC0A/OC1A#/AREF/PCINT0)_5") (pintype "unspecified"))
    )
    (net (code "43") (name "unconnected-(U4-PB1(MISO{slash}DO{slash}AIN1{slash}OC0B{slash}OC1A{slash}PCINT1)-Pad6)") (class "Default")
      (node (ref "U4") (pin "6") (pinfunction "PB1(MISO/DO/AIN1/OC0B/OC1A/PCINT1)_6") (pintype "unspecified"))
    )
    (net (code "44") (name "unconnected-(U4-PB2(SCK{slash}USCK{slash}SCL{slash}ADC1{slash}T0{slash}INT0{slash}PCINT2)-Pad7)") (class "Default")
      (node (ref "U4") (pin "7") (pinfunction "PB2(SCK/USCK/SCL/ADC1/T0/INT0/PCINT2)_7") (pintype "unspecified"))
    )
  )
)
